# 15VPart.net
KiCad netlist of a schematic drawn in EAGLE
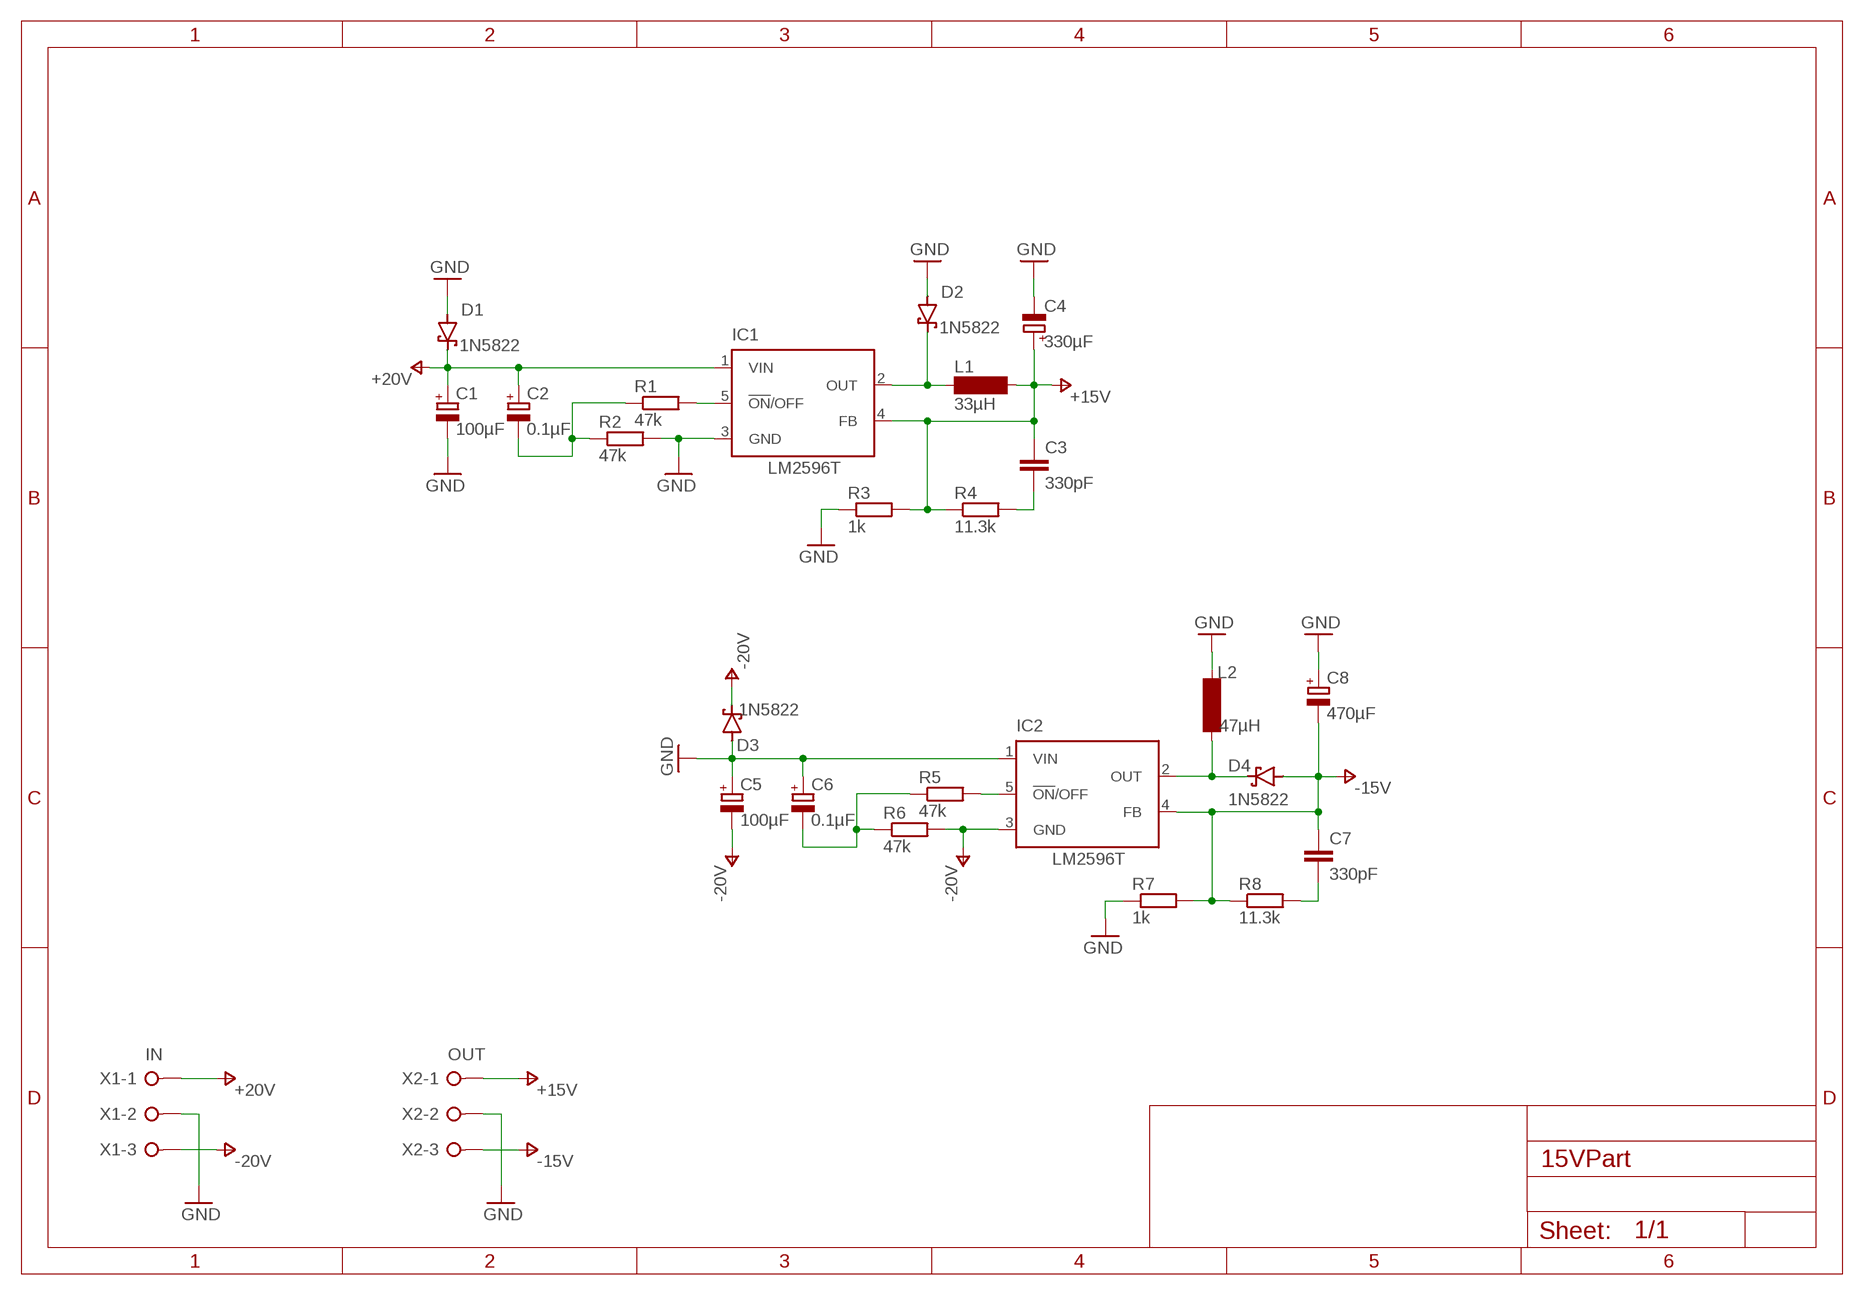
[diagram p0: schematic, sheet 1]

(export (version "E")
  (design (tool "Eeschema 10.0.6"))
  (components
    (comp (ref "C1")
      (value "100µF")
      (footprint "eagle-import:E2,5-6")
      (libsource (lib "eagle-import") (part "CPOL-EUE2.5-6"))
    )
    (comp (ref "C2")
      (value "0.1µF")
      (footprint "eagle-import:E1,8-4")
      (libsource (lib "eagle-import") (part "CPOL-EUE1.8-4"))
    )
    (comp (ref "C3")
      (value "330pF")
      (footprint "eagle-import:C050-024X044")
      (libsource (lib "eagle-import") (part "C-EU050-024X044"))
    )
    (comp (ref "C4")
      (value "330µF")
      (footprint "eagle-import:E3,5-8")
      (libsource (lib "eagle-import") (part "CPOL-EUE3.5-8"))
    )
    (comp (ref "C5")
      (value "100µF")
      (footprint "eagle-import:E2,5-6")
      (libsource (lib "eagle-import") (part "CPOL-EUE2.5-6"))
    )
    (comp (ref "C6")
      (value "0.1µF")
      (footprint "eagle-import:E1,8-4")
      (libsource (lib "eagle-import") (part "CPOL-EUE1.8-4"))
    )
    (comp (ref "C7")
      (value "330pF")
      (footprint "eagle-import:C050-024X044")
      (libsource (lib "eagle-import") (part "C-EU050-024X044"))
    )
    (comp (ref "C8")
      (value "470µF")
      (footprint "eagle-import:E3,5-8")
      (libsource (lib "eagle-import") (part "CPOL-EUE3.5-8"))
    )
    (comp (ref "D1")
      (value "1N5822")
      (footprint "eagle-import:C4111-15")
      (libsource (lib "eagle-import") (part "SCHOTTKY-DIODEC4111-15"))
    )
    (comp (ref "D2")
      (value "1N5822")
      (footprint "eagle-import:C4111-15")
      (libsource (lib "eagle-import") (part "SCHOTTKY-DIODEC4111-15"))
    )
    (comp (ref "D3")
      (value "1N5822")
      (footprint "eagle-import:C4111-15")
      (libsource (lib "eagle-import") (part "SCHOTTKY-DIODEC4111-15"))
    )
    (comp (ref "D4")
      (value "1N5822")
      (footprint "eagle-import:C4111-15")
      (libsource (lib "eagle-import") (part "SCHOTTKY-DIODEC4111-15"))
    )
    (comp (ref "IC1")
      (value "LM2596T")
      (footprint "eagle-import:T05D")
      (fields (field (name "MPN") "LM2596T-ADJ/LF02"))
      (libsource (lib "eagle-import") (part "LM2596T"))
    )
    (comp (ref "IC2")
      (value "LM2596T")
      (footprint "eagle-import:T05D")
      (fields (field (name "MPN") "LM2596T-ADJ/LF02"))
      (libsource (lib "eagle-import") (part "LM2596T"))
    )
    (comp (ref "L1")
      (value "33µH")
      (footprint "eagle-import:SD12-680")
      (fields (field (name "MF") "BUSSMANN") (field (name "MPN") "SD12-680"))
      (libsource (lib "eagle-import") (part "SD12-680"))
    )
    (comp (ref "L2")
      (value "47µH")
      (footprint "eagle-import:SD12-680")
      (fields (field (name "MF") "BUSSMANN") (field (name "MPN") "SD12-680"))
      (libsource (lib "eagle-import") (part "SD12-680"))
    )
    (comp (ref "R1")
      (value "47k")
      (footprint "eagle-import:0207_10")
      (libsource (lib "eagle-import") (part "R-EU_0207/10"))
    )
    (comp (ref "R2")
      (value "47k")
      (footprint "eagle-import:0207_10")
      (libsource (lib "eagle-import") (part "R-EU_0207/10"))
    )
    (comp (ref "R3")
      (value "1k")
      (footprint "eagle-import:0207_10")
      (libsource (lib "eagle-import") (part "R-EU_0207/10"))
    )
    (comp (ref "R4")
      (value "11.3k")
      (footprint "eagle-import:0207_10")
      (libsource (lib "eagle-import") (part "R-EU_0207/10"))
    )
    (comp (ref "R5")
      (value "47k")
      (footprint "eagle-import:0207_10")
      (libsource (lib "eagle-import") (part "R-EU_0207/10"))
    )
    (comp (ref "R6")
      (value "47k")
      (footprint "eagle-import:0207_10")
      (libsource (lib "eagle-import") (part "R-EU_0207/10"))
    )
    (comp (ref "R7")
      (value "1k")
      (footprint "eagle-import:0207_10")
      (libsource (lib "eagle-import") (part "R-EU_0207/10"))
    )
    (comp (ref "R8")
      (value "11.3k")
      (footprint "eagle-import:0207_10")
      (libsource (lib "eagle-import") (part "R-EU_0207/10"))
    )
    (comp (ref "X1")
      (value "IN")
      (footprint "eagle-import:W237-133")
      (libsource (lib "eagle-import") (part "W237-03P"))
    )
    (comp (ref "X2")
      (value "OUT")
      (footprint "eagle-import:W237-133")
      (libsource (lib "eagle-import") (part "W237-03P"))
    )
  )
  (nets
    (net (code "1") (name "+15V") (class "Default")
      (node (ref "C3") (pin "1") (pinfunction "1_1") (pintype "passive"))
      (node (ref "C4") (pin "+") (pinfunction "+_+") (pintype "passive"))
      (node (ref "IC1") (pin "4") (pinfunction "FB_4") (pintype "input"))
      (node (ref "L1") (pin "2") (pinfunction "2_2") (pintype "passive"))
      (node (ref "R3") (pin "2") (pinfunction "2_2") (pintype "passive"))
      (node (ref "R4") (pin "1") (pinfunction "1_1") (pintype "passive"))
      (node (ref "X2") (pin "1") (pinfunction "KL_1") (pintype "passive"))
    )
    (net (code "2") (name "+20V") (class "Default")
      (node (ref "C1") (pin "+") (pinfunction "+_+") (pintype "passive"))
      (node (ref "C2") (pin "+") (pinfunction "+_+") (pintype "passive"))
      (node (ref "D1") (pin "C") (pinfunction "C_C") (pintype "passive"))
      (node (ref "IC1") (pin "1") (pinfunction "VIN_1") (pintype "input"))
      (node (ref "X1") (pin "1") (pinfunction "KL_1") (pintype "passive"))
    )
    (net (code "3") (name "-15V") (class "Default")
      (node (ref "C7") (pin "1") (pinfunction "1_1") (pintype "passive"))
      (node (ref "C8") (pin "-") (pinfunction "-_-") (pintype "passive"))
      (node (ref "D4") (pin "A") (pinfunction "A_A") (pintype "passive"))
      (node (ref "IC2") (pin "4") (pinfunction "FB_4") (pintype "input"))
      (node (ref "R7") (pin "2") (pinfunction "2_2") (pintype "passive"))
      (node (ref "R8") (pin "1") (pinfunction "1_1") (pintype "passive"))
      (node (ref "X2") (pin "3") (pinfunction "KL_3") (pintype "passive"))
    )
    (net (code "4") (name "-20V") (class "Default")
      (node (ref "C5") (pin "-") (pinfunction "-_-") (pintype "passive"))
      (node (ref "D3") (pin "C") (pinfunction "C_C") (pintype "passive"))
      (node (ref "IC2") (pin "3") (pinfunction "GND_3") (pintype "power_in"))
      (node (ref "R6") (pin "2") (pinfunction "2_2") (pintype "passive"))
      (node (ref "X1") (pin "3") (pinfunction "KL_3") (pintype "passive"))
    )
    (net (code "5") (name "GND") (class "Default")
      (node (ref "C1") (pin "-") (pinfunction "-_-") (pintype "passive"))
      (node (ref "C4") (pin "-") (pinfunction "-_-") (pintype "passive"))
      (node (ref "C5") (pin "+") (pinfunction "+_+") (pintype "passive"))
      (node (ref "C6") (pin "+") (pinfunction "+_+") (pintype "passive"))
      (node (ref "C8") (pin "+") (pinfunction "+_+") (pintype "passive"))
      (node (ref "D1") (pin "A") (pinfunction "A_A") (pintype "passive"))
      (node (ref "D2") (pin "A") (pinfunction "A_A") (pintype "passive"))
      (node (ref "D3") (pin "A") (pinfunction "A_A") (pintype "passive"))
      (node (ref "IC1") (pin "3") (pinfunction "GND_3") (pintype "power_in"))
      (node (ref "IC2") (pin "1") (pinfunction "VIN_1") (pintype "input"))
      (node (ref "L2") (pin "2") (pinfunction "2_2") (pintype "passive"))
      (node (ref "R2") (pin "2") (pinfunction "2_2") (pintype "passive"))
      (node (ref "R3") (pin "1") (pinfunction "1_1") (pintype "passive"))
      (node (ref "R7") (pin "1") (pinfunction "1_1") (pintype "passive"))
      (node (ref "X1") (pin "2") (pinfunction "KL_2") (pintype "passive"))
      (node (ref "X2") (pin "2") (pinfunction "KL_2") (pintype "passive"))
    )
    (net (code "6") (name "Net-(C2-Pad-)") (class "Default")
      (node (ref "C2") (pin "-") (pinfunction "-_-") (pintype "passive"))
      (node (ref "R1") (pin "1") (pinfunction "1_1") (pintype "passive"))
      (node (ref "R2") (pin "1") (pinfunction "1_1") (pintype "passive"))
    )
    (net (code "7") (name "Net-(C3-Pad2)") (class "Default")
      (node (ref "C3") (pin "2") (pinfunction "2_2") (pintype "passive"))
      (node (ref "R4") (pin "2") (pinfunction "2_2") (pintype "passive"))
    )
    (net (code "8") (name "Net-(C6-Pad-)") (class "Default")
      (node (ref "C6") (pin "-") (pinfunction "-_-") (pintype "passive"))
      (node (ref "R5") (pin "1") (pinfunction "1_1") (pintype "passive"))
      (node (ref "R6") (pin "1") (pinfunction "1_1") (pintype "passive"))
    )
    (net (code "9") (name "Net-(C7-Pad2)") (class "Default")
      (node (ref "C7") (pin "2") (pinfunction "2_2") (pintype "passive"))
      (node (ref "R8") (pin "2") (pinfunction "2_2") (pintype "passive"))
    )
    (net (code "10") (name "Net-(IC1-OUT)") (class "Default")
      (node (ref "D2") (pin "C") (pinfunction "C_C") (pintype "passive"))
      (node (ref "IC1") (pin "2") (pinfunction "OUT_2") (pintype "output"))
      (node (ref "L1") (pin "1") (pinfunction "1_1") (pintype "passive"))
    )
    (net (code "11") (name "Net-(IC1-~{ON}{slash}OFF)") (class "Default")
      (node (ref "IC1") (pin "5") (pinfunction "~{ON}/OFF_5") (pintype "input"))
      (node (ref "R1") (pin "2") (pinfunction "2_2") (pintype "passive"))
    )
    (net (code "12") (name "Net-(IC2-OUT)") (class "Default")
      (node (ref "D4") (pin "C") (pinfunction "C_C") (pintype "passive"))
      (node (ref "IC2") (pin "2") (pinfunction "OUT_2") (pintype "output"))
      (node (ref "L2") (pin "1") (pinfunction "1_1") (pintype "passive"))
    )
    (net (code "13") (name "Net-(IC2-~{ON}{slash}OFF)") (class "Default")
      (node (ref "IC2") (pin "5") (pinfunction "~{ON}/OFF_5") (pintype "input"))
      (node (ref "R5") (pin "2") (pinfunction "2_2") (pintype "passive"))
    )
  )
)
